# Ethernet2.net
KiCad netlist of a schematic drawn in Altium Designer
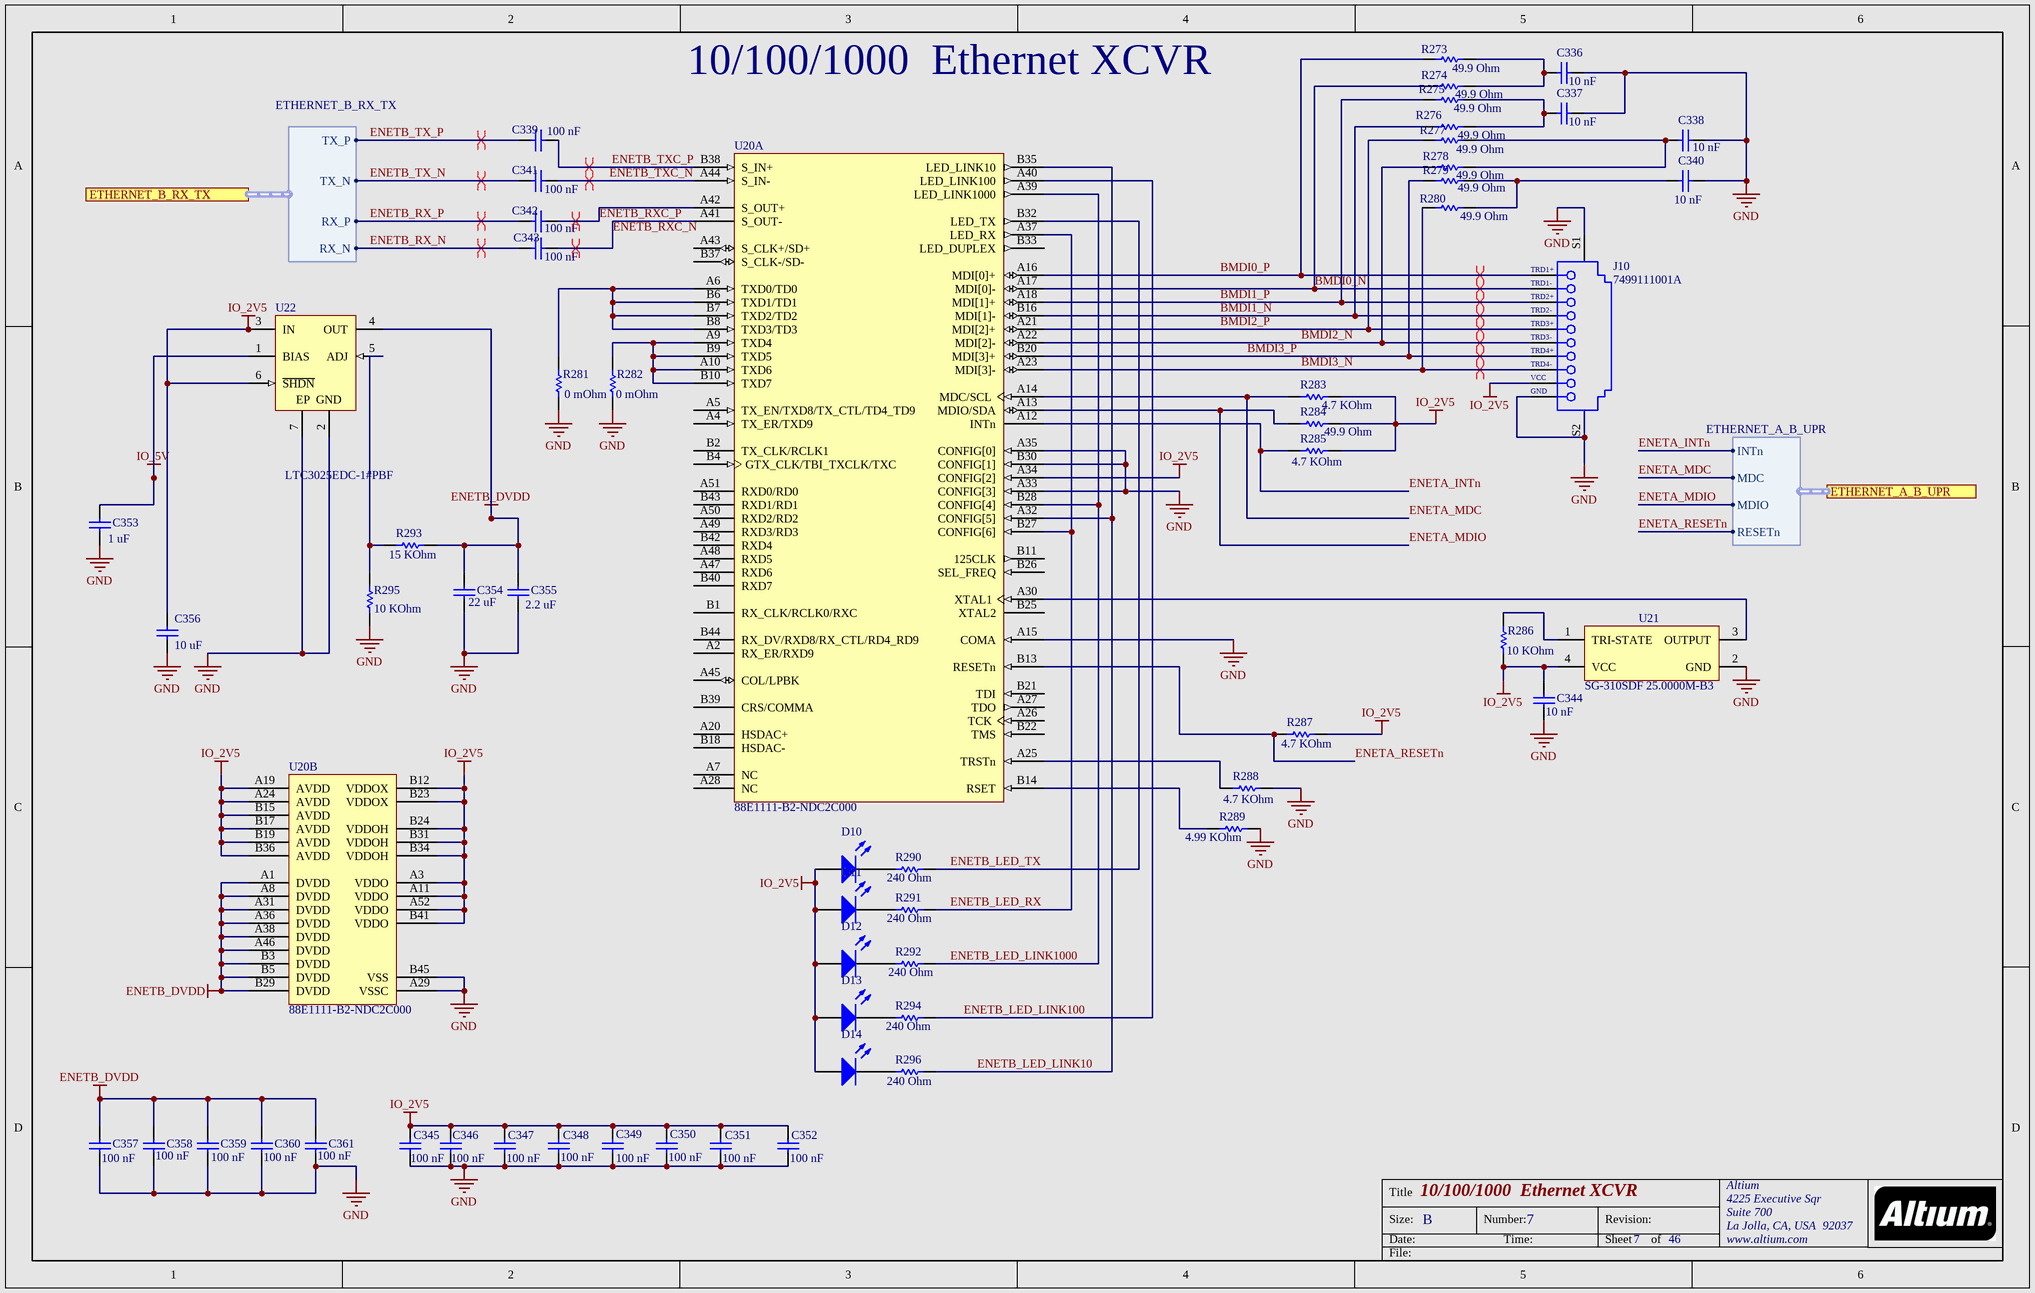
[diagram p0: Ethernet2.SchDoc]

(export (version "E")
  (design (tool "Eeschema 10.0.6"))
  (components
    (comp (ref "C336")
      (value "GRM155R71H103KA88D")
      (footprint "CAPC1005X55X25ML05T10")
      (description "Chip Capacitor, 10 nF, +/- 10%, 50 V, -55 to 125 degC, 0402 (1005 Metric), RoHS, Tape and Reel")
      (fields
        (field (name "TOLERANCE") "10%")
        (field (name "CAPACITANCE") "10 nF")
        (field (name "MANUFACTURER") "Basic Passives")
      )
      (libsource (lib "") (part "CAP-NP-2_1"))
    )
    (comp (ref "C337")
      (value "GRM155R71H103KA88D")
      (footprint "CAPC1005X55X25ML05T10")
      (description "Chip Capacitor, 10 nF, +/- 10%, 50 V, -55 to 125 degC, 0402 (1005 Metric), RoHS, Tape and Reel")
      (fields
        (field (name "TOLERANCE") "10%")
        (field (name "CAPACITANCE") "10 nF")
        (field (name "MANUFACTURER") "Basic Passives")
      )
      (libsource (lib "") (part "CAP-NP-2_1"))
    )
    (comp (ref "C338")
      (value "GRM155R71H103KA88D")
      (footprint "CAPC1005X55X25ML05T10")
      (description "Chip Capacitor, 10 nF, +/- 10%, 50 V, -55 to 125 degC, 0402 (1005 Metric), RoHS, Tape and Reel")
      (fields
        (field (name "TOLERANCE") "10%")
        (field (name "CAPACITANCE") "10 nF")
        (field (name "MANUFACTURER") "Basic Passives")
      )
      (libsource (lib "") (part "CAP-NP-2_1"))
    )
    (comp (ref "C339")
      (value "C1005X7R1E104M")
      (footprint "CAPC1005X55X10LL05")
      (description "Chip Capacitor, 0.1 uF, +/- 20%, 25 V, -55 to 125 degC, 0402 (1005 Metric), RoHS, Tape and Reel")
      (fields (field (name "TOLERANCE") "20%") (field (name "CAPACITANCE") "100 nF"))
      (libsource (lib "") (part "CAP-NP-2_1"))
    )
    (comp (ref "C340")
      (value "GRM155R71H103KA88D")
      (footprint "CAPC1005X55X25ML05T10")
      (description "Chip Capacitor, 10 nF, +/- 10%, 50 V, -55 to 125 degC, 0402 (1005 Metric), RoHS, Tape and Reel")
      (fields
        (field (name "TOLERANCE") "10%")
        (field (name "CAPACITANCE") "10 nF")
        (field (name "MANUFACTURER") "Basic Passives")
      )
      (libsource (lib "") (part "CAP-NP-2_1"))
    )
    (comp (ref "C341")
      (value "C1005X7R1E104M")
      (footprint "CAPC1005X55X10LL05")
      (description "Chip Capacitor, 0.1 uF, +/- 20%, 25 V, -55 to 125 degC, 0402 (1005 Metric), RoHS, Tape and Reel")
      (fields (field (name "TOLERANCE") "20%") (field (name "CAPACITANCE") "100 nF"))
      (libsource (lib "") (part "CAP-NP-2_1"))
    )
    (comp (ref "C342")
      (value "C1005X7R1E104M")
      (footprint "CAPC1005X55X10LL05")
      (description "Chip Capacitor, 0.1 uF, +/- 20%, 25 V, -55 to 125 degC, 0402 (1005 Metric), RoHS, Tape and Reel")
      (fields (field (name "TOLERANCE") "20%") (field (name "CAPACITANCE") "100 nF"))
      (libsource (lib "") (part "CAP-NP-2_1"))
    )
    (comp (ref "C343")
      (value "C1005X7R1E104M")
      (footprint "CAPC1005X55X10LL05")
      (description "Chip Capacitor, 0.1 uF, +/- 20%, 25 V, -55 to 125 degC, 0402 (1005 Metric), RoHS, Tape and Reel")
      (fields (field (name "TOLERANCE") "20%") (field (name "CAPACITANCE") "100 nF"))
      (libsource (lib "") (part "CAP-NP-2_1"))
    )
    (comp (ref "C344")
      (value "GRM155R71H103KA88D")
      (footprint "CAPC1005X55X25ML05T10")
      (description "Chip Capacitor, 10 nF, +/- 10%, 50 V, -55 to 125 degC, 0402 (1005 Metric), RoHS, Tape and Reel")
      (fields
        (field (name "TOLERANCE") "10%")
        (field (name "CAPACITANCE") "10 nF")
        (field (name "MANUFACTURER") "Basic Passives")
      )
      (libsource (lib "") (part "CAP-NP-2_1"))
    )
    (comp (ref "C345")
      (value "C1005X7R1E104M")
      (footprint "CAPC1005X55X10LL05")
      (description "Chip Capacitor, 0.1 uF, +/- 20%, 25 V, -55 to 125 degC, 0402 (1005 Metric), RoHS, Tape and Reel")
      (fields (field (name "TOLERANCE") "20%") (field (name "CAPACITANCE") "100 nF"))
      (libsource (lib "") (part "CAP-NP-2_1"))
    )
    (comp (ref "C346")
      (value "C1005X7R1E104M")
      (footprint "CAPC1005X55X10LL05")
      (description "Chip Capacitor, 0.1 uF, +/- 20%, 25 V, -55 to 125 degC, 0402 (1005 Metric), RoHS, Tape and Reel")
      (fields (field (name "TOLERANCE") "20%") (field (name "CAPACITANCE") "100 nF"))
      (libsource (lib "") (part "CAP-NP-2_1"))
    )
    (comp (ref "C347")
      (value "C1005X7R1E104M")
      (footprint "CAPC1005X55X10LL05")
      (description "Chip Capacitor, 0.1 uF, +/- 20%, 25 V, -55 to 125 degC, 0402 (1005 Metric), RoHS, Tape and Reel")
      (fields (field (name "TOLERANCE") "20%") (field (name "CAPACITANCE") "100 nF"))
      (libsource (lib "") (part "CAP-NP-2_1"))
    )
    (comp (ref "C348")
      (value "C1005X7R1E104M")
      (footprint "CAPC1005X55X10LL05")
      (description "Chip Capacitor, 0.1 uF, +/- 20%, 25 V, -55 to 125 degC, 0402 (1005 Metric), RoHS, Tape and Reel")
      (fields (field (name "TOLERANCE") "20%") (field (name "CAPACITANCE") "100 nF"))
      (libsource (lib "") (part "CAP-NP-2_1"))
    )
    (comp (ref "C349")
      (value "C1005X7R1E104M")
      (footprint "CAPC1005X55X10LL05")
      (description "Chip Capacitor, 0.1 uF, +/- 20%, 25 V, -55 to 125 degC, 0402 (1005 Metric), RoHS, Tape and Reel")
      (fields (field (name "TOLERANCE") "20%") (field (name "CAPACITANCE") "100 nF"))
      (libsource (lib "") (part "CAP-NP-2_1"))
    )
    (comp (ref "C350")
      (value "C1005X7R1E104M")
      (footprint "CAPC1005X55X10LL05")
      (description "Chip Capacitor, 0.1 uF, +/- 20%, 25 V, -55 to 125 degC, 0402 (1005 Metric), RoHS, Tape and Reel")
      (fields (field (name "TOLERANCE") "20%") (field (name "CAPACITANCE") "100 nF"))
      (libsource (lib "") (part "CAP-NP-2_1"))
    )
    (comp (ref "C351")
      (value "C1005X7R1E104M")
      (footprint "CAPC1005X55X10LL05")
      (description "Chip Capacitor, 0.1 uF, +/- 20%, 25 V, -55 to 125 degC, 0402 (1005 Metric), RoHS, Tape and Reel")
      (fields (field (name "TOLERANCE") "20%") (field (name "CAPACITANCE") "100 nF"))
      (libsource (lib "") (part "CAP-NP-2_1"))
    )
    (comp (ref "C352")
      (value "C1005X7R1E104M")
      (footprint "CAPC1005X55X10LL05")
      (description "Chip Capacitor, 0.1 uF, +/- 20%, 25 V, -55 to 125 degC, 0402 (1005 Metric), RoHS, Tape and Reel")
      (fields (field (name "TOLERANCE") "20%") (field (name "CAPACITANCE") "100 nF"))
      (libsource (lib "") (part "CAP-NP-2_1"))
    )
    (comp (ref "C353")
      (value "CGB2A1X5R1E105K033BC")
      (footprint "CAPC1005X33X10LL5")
      (description "Chip Capacitor, 1 uF, +/- 10%, 25 V, -55 to 85 degC, 0402 (1005 Metric), RoHS, Tape and Reel")
      (fields (field (name "CAPACITANCE") "1 uF") (field (name "TOLERANCE") "10%"))
      (libsource (lib "Altium Content Vault") (part "CAP-NP-2"))
    )
    (comp (ref "C354")
      (value "GRM31CR61E226KE15L")
      (footprint "CAPC3216X180X55ML20T25")
      (description "Chip Capacitor, 22 uF, +/- 10%, 25 V, -55 to 85 degC, 1206 (3216 Metric), RoHS, Tape and Reel")
      (fields (field (name "TOLERANCE") "10%") (field (name "CAPACITANCE") "22 uF"))
      (libsource (lib "") (part "CAP-NP-2_1"))
    )
    (comp (ref "C355")
      (value "GRM188R61A225KE34x")
      (footprint "CAPC1608X90X35ML10T15")
      (description "Chip Capacitor, 2.2 uF, +/- 10%, 10 V, -55 to 85 degC, 0603 (1608 Metric), RoHS, Tape and Reel")
      (fields (field (name "TOLERANCE") "10%") (field (name "CAPACITANCE") "2.2 uF"))
      (libsource (lib "Altium Content Vault") (part "CAP-NP-2"))
    )
    (comp (ref "C356")
      (value "C2012X5R1C106K085AC")
      (footprint "CAPC2013X100X20NL20")
      (description "Chip Capacitor, 10 uF, +/- 10%, 16 V, -55 to 85 degC, 0805 (2012 Metric), RoHS, Tape and Reel")
      (fields (field (name "TOLERANCE") "10%") (field (name "CAPACITANCE") "10 uF"))
      (libsource (lib "Altium Content Vault") (part "CAP-NP-2"))
    )
    (comp (ref "C357")
      (value "C1005X7R1E104M")
      (footprint "CAPC1005X55X10LL05")
      (description "Chip Capacitor, 0.1 uF, +/- 20%, 25 V, -55 to 125 degC, 0402 (1005 Metric), RoHS, Tape and Reel")
      (fields (field (name "TOLERANCE") "20%") (field (name "CAPACITANCE") "100 nF"))
      (libsource (lib "") (part "CAP-NP-2_1"))
    )
    (comp (ref "C358")
      (value "C1005X7R1E104M")
      (footprint "CAPC1005X55X10LL05")
      (description "Chip Capacitor, 0.1 uF, +/- 20%, 25 V, -55 to 125 degC, 0402 (1005 Metric), RoHS, Tape and Reel")
      (fields (field (name "TOLERANCE") "20%") (field (name "CAPACITANCE") "100 nF"))
      (libsource (lib "") (part "CAP-NP-2_1"))
    )
    (comp (ref "C359")
      (value "C1005X7R1E104M")
      (footprint "CAPC1005X55X10LL05")
      (description "Chip Capacitor, 0.1 uF, +/- 20%, 25 V, -55 to 125 degC, 0402 (1005 Metric), RoHS, Tape and Reel")
      (fields (field (name "TOLERANCE") "20%") (field (name "CAPACITANCE") "100 nF"))
      (libsource (lib "") (part "CAP-NP-2_1"))
    )
    (comp (ref "C360")
      (value "C1005X7R1E104M")
      (footprint "CAPC1005X55X10LL05")
      (description "Chip Capacitor, 0.1 uF, +/- 20%, 25 V, -55 to 125 degC, 0402 (1005 Metric), RoHS, Tape and Reel")
      (fields (field (name "TOLERANCE") "20%") (field (name "CAPACITANCE") "100 nF"))
      (libsource (lib "") (part "CAP-NP-2_1"))
    )
    (comp (ref "C361")
      (value "C1005X7R1E104M")
      (footprint "CAPC1005X55X10LL05")
      (description "Chip Capacitor, 0.1 uF, +/- 20%, 25 V, -55 to 125 degC, 0402 (1005 Metric), RoHS, Tape and Reel")
      (fields (field (name "TOLERANCE") "20%") (field (name "CAPACITANCE") "100 nF"))
      (libsource (lib "") (part "CAP-NP-2_1"))
    )
    (comp (ref "D10")
      (value "150060VS75000")
      (footprint "0603_A")
      (description "SMD mono-color Chip LED, WL-SMCW, Bright Green")
      (fields (field (name "MANUFACTURER") "Wuerth Elektronik"))
      (libsource (lib "Altium Content Vault") (part "CMP-1426-00006-1"))
    )
    (comp (ref "D11")
      (value "150060VS75000")
      (footprint "0603_A")
      (description "SMD mono-color Chip LED, WL-SMCW, Bright Green")
      (fields (field (name "MANUFACTURER") "Wuerth Elektronik"))
      (libsource (lib "Altium Content Vault") (part "CMP-1426-00006-1"))
    )
    (comp (ref "D12")
      (value "150060VS75000")
      (footprint "0603_A")
      (description "SMD mono-color Chip LED, WL-SMCW, Bright Green")
      (fields (field (name "MANUFACTURER") "Wuerth Elektronik"))
      (libsource (lib "Altium Content Vault") (part "CMP-1426-00006-1"))
    )
    (comp (ref "D13")
      (value "150060VS75000")
      (footprint "0603_A")
      (description "SMD mono-color Chip LED, WL-SMCW, Bright Green")
      (fields (field (name "MANUFACTURER") "Wuerth Elektronik"))
      (libsource (lib "Altium Content Vault") (part "CMP-1426-00006-1"))
    )
    (comp (ref "D14")
      (value "150060VS75000")
      (footprint "0603_A")
      (description "SMD mono-color Chip LED, WL-SMCW, Bright Green")
      (fields (field (name "MANUFACTURER") "Wuerth Elektronik"))
      (libsource (lib "Altium Content Vault") (part "CMP-1426-00006-1"))
    )
    (comp (ref "J10")
      (value "7499111001A")
      (footprint "WE-7499111001A_V")
      (description "RJ45 LAN Transformer, Modular JACK, 0 to 70 degC, 10-Pin THD, RoHS, Tube")
      (libsource (lib "Altium Content Vault") (part "RJ45-10-2SHLD_A"))
    )
    (comp (ref "R273")
      (value "NRC04F49R9TRF")
      (footprint "RESC1005X35X25NL8T10")
      (description "Chip Resistor, 49.9 Ohm, +/- 1%, 0.06 W, -55 to 155 degC, 0402 (1005 Metric), RoHS, Tape and Reel")
      (fields (field (name "TOLERANCE") "1%") (field (name "RESISTANCE") "49.9 Ohm"))
      (libsource (lib "Altium Content Vault") (part "CMP-1599-00001-2"))
    )
    (comp (ref "R274")
      (value "NRC04F49R9TRF")
      (footprint "RESC1005X35X25NL8T10")
      (description "Chip Resistor, 49.9 Ohm, +/- 1%, 0.06 W, -55 to 155 degC, 0402 (1005 Metric), RoHS, Tape and Reel")
      (fields (field (name "TOLERANCE") "1%") (field (name "RESISTANCE") "49.9 Ohm"))
      (libsource (lib "Altium Content Vault") (part "RES-2"))
    )
    (comp (ref "R275")
      (value "NRC04F49R9TRF")
      (footprint "RESC1005X35X25NL8T10")
      (description "Chip Resistor, 49.9 Ohm, +/- 1%, 0.06 W, -55 to 155 degC, 0402 (1005 Metric), RoHS, Tape and Reel")
      (fields (field (name "TOLERANCE") "1%") (field (name "RESISTANCE") "49.9 Ohm"))
      (libsource (lib "Altium Content Vault") (part "RES-2"))
    )
    (comp (ref "R276")
      (value "NRC04F49R9TRF")
      (footprint "RESC1005X35X25NL8T10")
      (description "Chip Resistor, 49.9 Ohm, +/- 1%, 0.06 W, -55 to 155 degC, 0402 (1005 Metric), RoHS, Tape and Reel")
      (fields (field (name "TOLERANCE") "1%") (field (name "RESISTANCE") "49.9 Ohm"))
      (libsource (lib "Altium Content Vault") (part "CMP-1599-00001-2"))
    )
    (comp (ref "R277")
      (value "NRC04F49R9TRF")
      (footprint "RESC1005X35X25NL8T10")
      (description "Chip Resistor, 49.9 Ohm, +/- 1%, 0.06 W, -55 to 155 degC, 0402 (1005 Metric), RoHS, Tape and Reel")
      (fields (field (name "TOLERANCE") "1%") (field (name "RESISTANCE") "49.9 Ohm"))
      (libsource (lib "Altium Content Vault") (part "RES-2"))
    )
    (comp (ref "R278")
      (value "NRC04F49R9TRF")
      (footprint "RESC1005X35X25NL8T10")
      (description "Chip Resistor, 49.9 Ohm, +/- 1%, 0.06 W, -55 to 155 degC, 0402 (1005 Metric), RoHS, Tape and Reel")
      (fields (field (name "TOLERANCE") "1%") (field (name "RESISTANCE") "49.9 Ohm"))
      (libsource (lib "Altium Content Vault") (part "RES-2"))
    )
    (comp (ref "R279")
      (value "NRC04F49R9TRF")
      (footprint "RESC1005X35X25NL8T10")
      (description "Chip Resistor, 49.9 Ohm, +/- 1%, 0.06 W, -55 to 155 degC, 0402 (1005 Metric), RoHS, Tape and Reel")
      (fields (field (name "TOLERANCE") "1%") (field (name "RESISTANCE") "49.9 Ohm"))
      (libsource (lib "Altium Content Vault") (part "CMP-1599-00001-2"))
    )
    (comp (ref "R280")
      (value "NRC04F49R9TRF")
      (footprint "RESC1005X35X25NL8T10")
      (description "Chip Resistor, 49.9 Ohm, +/- 1%, 0.06 W, -55 to 155 degC, 0402 (1005 Metric), RoHS, Tape and Reel")
      (fields (field (name "TOLERANCE") "1%") (field (name "RESISTANCE") "49.9 Ohm"))
      (libsource (lib "Altium Content Vault") (part "RES-2"))
    )
    (comp (ref "R281")
      (value "ERJ-2GE0R00X")
      (footprint "RESC1005X40X25ML05T05")
      (description "Chip Resistor, 0 mOhm, +/- 5%, 100 mW, -55 to 155 degC, 0402 (1005 Metric), RoHS, Tape and Reel")
      (fields
        (field (name "TOLERANCE") "5%")
        (field (name "RESISTANCE") "0 mOhm")
        (field (name "MANUFACTURER") "Basic Passives")
      )
      (libsource (lib "Altium Content Vault") (part "RES-2"))
    )
    (comp (ref "R282")
      (value "ERJ-2GE0R00X")
      (footprint "RESC1005X40X25ML05T05")
      (description "Chip Resistor, 0 mOhm, +/- 5%, 100 mW, -55 to 155 degC, 0402 (1005 Metric), RoHS, Tape and Reel")
      (fields
        (field (name "TOLERANCE") "5%")
        (field (name "RESISTANCE") "0 mOhm")
        (field (name "MANUFACTURER") "Basic Passives")
      )
      (libsource (lib "Altium Content Vault") (part "RES-2"))
    )
    (comp (ref "R283")
      (value "ERJ-2RKF4701X")
      (footprint "RESC1005X40X25LL05T05")
      (description "Chip Resistor, 4.7 KOhm, +/- 1%, 0.1 W, -55 to 155 degC, 0402 (1005 Metric), RoHS, Tape and Reel")
      (fields (field (name "TOLERANCE") "1%") (field (name "RESISTANCE") "4.7 KOhm"))
      (libsource (lib "Altium Content Vault") (part "RES-2"))
    )
    (comp (ref "R284")
      (value "NRC04F49R9TRF")
      (footprint "RESC1005X35X25NL8T10")
      (description "Chip Resistor, 49.9 Ohm, +/- 1%, 0.06 W, -55 to 155 degC, 0402 (1005 Metric), RoHS, Tape and Reel")
      (fields (field (name "TOLERANCE") "1%") (field (name "RESISTANCE") "49.9 Ohm"))
      (libsource (lib "Altium Content Vault") (part "CMP-1599-00001-2"))
    )
    (comp (ref "R285")
      (value "ERJ-2RKF4701X")
      (footprint "RESC1005X40X25LL05T05")
      (description "Chip Resistor, 4.7 KOhm, +/- 1%, 0.1 W, -55 to 155 degC, 0402 (1005 Metric), RoHS, Tape and Reel")
      (fields (field (name "TOLERANCE") "1%") (field (name "RESISTANCE") "4.7 KOhm"))
      (libsource (lib "Altium Content Vault") (part "RES-2"))
    )
    (comp (ref "R286")
      (value "ERJ-2RKF1002X")
      (footprint "RESC1005X40X25NL05T05")
      (description "Chip Resistor, 10 KOhm, +/- 1%, 100 mW, -55 to 155 degC, 0402 (1005 Metric), RoHS, Tape and Reel")
      (fields
        (field (name "TOLERANCE") "1%")
        (field (name "RESISTANCE") "10 KOhm")
        (field (name "MANUFACTURER") "Basic Passives")
      )
      (libsource (lib "Altium Content Vault") (part "RES-2"))
    )
    (comp (ref "R287")
      (value "ERJ-2RKF4701X")
      (footprint "RESC1005X40X25LL05T05")
      (description "Chip Resistor, 4.7 KOhm, +/- 1%, 0.1 W, -55 to 155 degC, 0402 (1005 Metric), RoHS, Tape and Reel")
      (fields (field (name "TOLERANCE") "1%") (field (name "RESISTANCE") "4.7 KOhm"))
      (libsource (lib "Altium Content Vault") (part "RES-2"))
    )
    (comp (ref "R288")
      (value "ERJ-2RKF4701X")
      (footprint "RESC1005X40X25LL05T05")
      (description "Chip Resistor, 4.7 KOhm, +/- 1%, 0.1 W, -55 to 155 degC, 0402 (1005 Metric), RoHS, Tape and Reel")
      (fields (field (name "TOLERANCE") "1%") (field (name "RESISTANCE") "4.7 KOhm"))
      (libsource (lib "Altium Content Vault") (part "RES-2"))
    )
    (comp (ref "R289")
      (value "ERJ-2RKF4991X")
      (footprint "RESC1005X40X25NL05T05")
      (description "Chip Resistor, 4.99 KOhm, +/- 1%, 100 mW, -55 to 155 degC, 0402 (1005 Metric), RoHS, Tape and Reel")
      (fields
        (field (name "TOLERANCE") "1%")
        (field (name "RESISTANCE") "4.99 KOhm")
        (field (name "MANUFACTURER") "Basic Passives")
      )
      (libsource (lib "Altium Content Vault") (part "RES-2"))
    )
    (comp (ref "R290")
      (value "ERJ-2RKF2400X")
      (footprint "RESC1005X40X25NL05T05")
      (description "Chip Resistor, 240 Ohm, +/- 1%, 100 mW, -55 to 155 degC, 0402 (1005 Metric), RoHS, Tape and Reel")
      (fields (field (name "TOLERANCE") "1%") (field (name "RESISTANCE") "240 Ohm"))
      (libsource (lib "Altium Content Vault") (part "RES-2"))
    )
    (comp (ref "R291")
      (value "ERJ-2RKF2400X")
      (footprint "RESC1005X40X25NL05T05")
      (description "Chip Resistor, 240 Ohm, +/- 1%, 100 mW, -55 to 155 degC, 0402 (1005 Metric), RoHS, Tape and Reel")
      (fields (field (name "TOLERANCE") "1%") (field (name "RESISTANCE") "240 Ohm"))
      (libsource (lib "Altium Content Vault") (part "RES-2"))
    )
    (comp (ref "R292")
      (value "ERJ-2RKF2400X")
      (footprint "RESC1005X40X25NL05T05")
      (description "Chip Resistor, 240 Ohm, +/- 1%, 100 mW, -55 to 155 degC, 0402 (1005 Metric), RoHS, Tape and Reel")
      (fields (field (name "TOLERANCE") "1%") (field (name "RESISTANCE") "240 Ohm"))
      (libsource (lib "Altium Content Vault") (part "RES-2"))
    )
    (comp (ref "R293")
      (value "ERJ-2RKF1502X")
      (footprint "RESC1005X40X25ML05T05")
      (description "Chip Resistor, 15 KOhm, +/- 1%, 100 mW, -55 to 155 degC, 0402 (1005 Metric), RoHS, Tape and Reel")
      (fields
        (field (name "RESISTANCE") "15 KOhm")
        (field (name "TOLERANCE") "1%")
        (field (name "MANUFACTURER") "Basic Passives")
      )
      (libsource (lib "Altium Content Vault") (part "RES-2"))
    )
    (comp (ref "R294")
      (value "ERJ-2RKF2400X")
      (footprint "RESC1005X40X25NL05T05")
      (description "Chip Resistor, 240 Ohm, +/- 1%, 100 mW, -55 to 155 degC, 0402 (1005 Metric), RoHS, Tape and Reel")
      (fields (field (name "TOLERANCE") "1%") (field (name "RESISTANCE") "240 Ohm"))
      (libsource (lib "Altium Content Vault") (part "RES-2"))
    )
    (comp (ref "R295")
      (value "ERJ-2RKF1002X")
      (footprint "RESC1005X40X25NL05T05")
      (description "Chip Resistor, 10 KOhm, +/- 1%, 100 mW, -55 to 155 degC, 0402 (1005 Metric), RoHS, Tape and Reel")
      (fields
        (field (name "TOLERANCE") "1%")
        (field (name "RESISTANCE") "10 KOhm")
        (field (name "MANUFACTURER") "Basic Passives")
      )
      (libsource (lib "Altium Content Vault") (part "RES-2"))
    )
    (comp (ref "R296")
      (value "ERJ-2RKF2400X")
      (footprint "RESC1005X40X25NL05T05")
      (description "Chip Resistor, 240 Ohm, +/- 1%, 100 mW, -55 to 155 degC, 0402 (1005 Metric), RoHS, Tape and Reel")
      (fields (field (name "TOLERANCE") "1%") (field (name "RESISTANCE") "240 Ohm"))
      (libsource (lib "Altium Content Vault") (part "RES-2"))
    )
    (comp (ref "U20")
      (value "88E1111-B2-NDC2C000")
      (footprint "MARV-NDC96")
      (description "Integrated 10/100/1000 Ultra Gigabit Ethernet Transceiver, Commercial Grade, 96-Pin QFN, RoHS")
      (libsource (lib "Altium Content Vault") (part "MARV-88E1111-NDC96"))
    )
    (comp (ref "U21")
      (value "SG-310SDF 25.0000M-B3")
      (footprint "EPSON-SG-310-4_V")
      (description "Crystal Oscillator (SPXO), 2.5 V, 25 MHz, -20 to 70 degC, 4-Pin SMD, RoHS, Tape and Reel")
      (libsource (lib "Altium Content Vault") (part "XTAL-1-3-4_B"))
    )
    (comp (ref "U22")
      (value "LTC3025EDC-1#PBF")
      (footprint "LT-DC6-6_V")
      (fields (field (name "MANUFACTURER") "Linear Technology"))
      (libsource (lib "Altium Content Vault") (part "LT-LTC302-DC6-6"))
    )
  )
  (nets
    (net (code "3") (name "/BMDI0_N") (class "Default")
      (node (ref "J10") (pin "2") (pinfunction "TRD1-_2") (pintype "passive"))
      (node (ref "R274") (pin "1") (pinfunction "1_1") (pintype "passive"))
      (node (ref "U20") (pin "A17") (pinfunction "MDI[0]-_A17") (pintype "bidirectional"))
    )
    (net (code "4") (name "/BMDI0_P") (class "Default")
      (node (ref "J10") (pin "1") (pinfunction "TRD1+_1") (pintype "passive"))
      (node (ref "R273") (pin "1") (pinfunction "1_1") (pintype "passive"))
      (node (ref "U20") (pin "A16") (pinfunction "MDI[0]+_A16") (pintype "bidirectional"))
    )
    (net (code "5") (name "/BMDI1_N") (class "Default")
      (node (ref "J10") (pin "4") (pinfunction "TRD2-_4") (pintype "passive"))
      (node (ref "R276") (pin "1") (pinfunction "1_1") (pintype "passive"))
      (node (ref "U20") (pin "B16") (pinfunction "MDI[1]-_B16") (pintype "bidirectional"))
    )
    (net (code "6") (name "/BMDI1_P") (class "Default")
      (node (ref "J10") (pin "3") (pinfunction "TRD2+_3") (pintype "passive"))
      (node (ref "R275") (pin "1") (pinfunction "1_1") (pintype "passive"))
      (node (ref "U20") (pin "A18") (pinfunction "MDI[1]+_A18") (pintype "bidirectional"))
    )
    (net (code "7") (name "/BMDI2_N") (class "Default")
      (node (ref "J10") (pin "6") (pinfunction "TRD3-_6") (pintype "passive"))
      (node (ref "R278") (pin "1") (pinfunction "1_1") (pintype "passive"))
      (node (ref "U20") (pin "A22") (pinfunction "MDI[2]-_A22") (pintype "bidirectional"))
    )
    (net (code "8") (name "/BMDI2_P") (class "Default")
      (node (ref "J10") (pin "5") (pinfunction "TRD3+_5") (pintype "passive"))
      (node (ref "R277") (pin "1") (pinfunction "1_1") (pintype "passive"))
      (node (ref "U20") (pin "A21") (pinfunction "MDI[2]+_A21") (pintype "bidirectional"))
    )
    (net (code "9") (name "/BMDI3_N") (class "Default")
      (node (ref "J10") (pin "8") (pinfunction "TRD4-_8") (pintype "passive"))
      (node (ref "R280") (pin "1") (pinfunction "1_1") (pintype "passive"))
      (node (ref "U20") (pin "A23") (pinfunction "MDI[3]-_A23") (pintype "bidirectional"))
    )
    (net (code "10") (name "/BMDI3_P") (class "Default")
      (node (ref "J10") (pin "7") (pinfunction "TRD4+_7") (pintype "passive"))
      (node (ref "R279") (pin "1") (pinfunction "1_1") (pintype "passive"))
      (node (ref "U20") (pin "B20") (pinfunction "MDI[3]+_B20") (pintype "bidirectional"))
    )
    (net (code "11") (name "/ENETA_INTn") (class "Default")
      (node (ref "R285") (pin "1") (pinfunction "1_1") (pintype "passive"))
      (node (ref "U20") (pin "A12") (pinfunction "INTn_A12") (pintype "passive"))
    )
    (net (code "12") (name "/ENETA_MDC") (class "Default")
      (node (ref "R283") (pin "1") (pinfunction "1_1") (pintype "passive"))
      (node (ref "U20") (pin "A14") (pinfunction "MDC/SCL_A14") (pintype "input"))
    )
    (net (code "13") (name "/ENETA_MDIO") (class "Default")
      (node (ref "R284") (pin "1") (pinfunction "1_1") (pintype "passive"))
      (node (ref "U20") (pin "A13") (pinfunction "MDIO/SDA_A13") (pintype "bidirectional"))
    )
    (net (code "14") (name "/ENETA_RESETn") (class "Default")
      (node (ref "R287") (pin "1") (pinfunction "1_1") (pintype "passive"))
      (node (ref "U20") (pin "B13") (pinfunction "RESETn_B13") (pintype "input"))
    )
    (net (code "15") (name "/ENETB_LED_LINK10") (class "Default")
      (node (ref "R296") (pin "2") (pinfunction "2_2") (pintype "passive"))
      (node (ref "U20") (pin "A32") (pinfunction "CONFIG[5]_A32") (pintype "input"))
      (node (ref "U20") (pin "B35") (pinfunction "LED_LINK10_B35") (pintype "output"))
    )
    (net (code "16") (name "/ENETB_LED_LINK100") (class "Default")
      (node (ref "R294") (pin "2") (pinfunction "2_2") (pintype "passive"))
      (node (ref "U20") (pin "A40") (pinfunction "LED_LINK100_A40") (pintype "output"))
    )
    (net (code "17") (name "/ENETB_LED_LINK1000") (class "Default")
      (node (ref "R292") (pin "2") (pinfunction "2_2") (pintype "passive"))
      (node (ref "U20") (pin "A39") (pinfunction "LED_LINK1000_A39") (pintype "output"))
      (node (ref "U20") (pin "B28") (pinfunction "CONFIG[4]_B28") (pintype "input"))
    )
    (net (code "18") (name "/ENETB_LED_RX") (class "Default")
      (node (ref "R291") (pin "2") (pinfunction "2_2") (pintype "passive"))
      (node (ref "U20") (pin "A37") (pinfunction "LED_RX_A37") (pintype "output"))
      (node (ref "U20") (pin "B27") (pinfunction "CONFIG[6]_B27") (pintype "input"))
    )
    (net (code "19") (name "/ENETB_LED_TX") (class "Default")
      (node (ref "R290") (pin "2") (pinfunction "2_2") (pintype "passive"))
      (node (ref "U20") (pin "B32") (pinfunction "LED_TX_B32") (pintype "output"))
    )
    (net (code "20") (name "/ENETB_RXC_N") (class "Default")
      (node (ref "C343") (pin "2") (pinfunction "2_2") (pintype "passive"))
      (node (ref "U20") (pin "A41") (pinfunction "S_OUT-_A41") (pintype "tri_state"))
    )
    (net (code "21") (name "/ENETB_RXC_P") (class "Default")
      (node (ref "C342") (pin "2") (pinfunction "2_2") (pintype "passive"))
      (node (ref "U20") (pin "A42") (pinfunction "S_OUT+_A42") (pintype "tri_state"))
    )
    (net (code "22") (name "/ENETB_RX_N") (class "Default")
      (node (ref "C343") (pin "1") (pinfunction "1_1") (pintype "passive"))
    )
    (net (code "23") (name "/ENETB_RX_P") (class "Default")
      (node (ref "C342") (pin "1") (pinfunction "1_1") (pintype "passive"))
    )
    (net (code "24") (name "/ENETB_TXC_N") (class "Default")
      (node (ref "C341") (pin "2") (pinfunction "2_2") (pintype "passive"))
      (node (ref "U20") (pin "A44") (pinfunction "S_IN-_A44") (pintype "input"))
    )
    (net (code "25") (name "/ENETB_TXC_P") (class "Default")
      (node (ref "C339") (pin "2") (pinfunction "2_2") (pintype "passive"))
      (node (ref "U20") (pin "B38") (pinfunction "S_IN+_B38") (pintype "input"))
    )
    (net (code "26") (name "/ENETB_TX_N") (class "Default")
      (node (ref "C341") (pin "1") (pinfunction "1_1") (pintype "passive"))
    )
    (net (code "27") (name "/ENETB_TX_P") (class "Default")
      (node (ref "C339") (pin "1") (pinfunction "1_1") (pintype "passive"))
    )
    (net (code "30") (name "ENETB_DVDD") (class "Default")
      (node (ref "C354") (pin "2") (pinfunction "2_2") (pintype "passive"))
      (node (ref "C355") (pin "2") (pinfunction "2_2") (pintype "passive"))
      (node (ref "C357") (pin "2") (pinfunction "2_2") (pintype "passive"))
      (node (ref "C358") (pin "2") (pinfunction "2_2") (pintype "passive"))
      (node (ref "C359") (pin "2") (pinfunction "2_2") (pintype "passive"))
      (node (ref "C360") (pin "2") (pinfunction "2_2") (pintype "passive"))
      (node (ref "C361") (pin "2") (pinfunction "2_2") (pintype "passive"))
      (node (ref "R293") (pin "2") (pinfunction "2_2") (pintype "passive"))
      (node (ref "U20") (pin "A1") (pinfunction "DVDD_A1") (pintype "power_in"))
      (node (ref "U20") (pin "A31") (pinfunction "DVDD_A31") (pintype "power_in"))
      (node (ref "U20") (pin "A36") (pinfunction "DVDD_A36") (pintype "power_in"))
      (node (ref "U20") (pin "A38") (pinfunction "DVDD_A38") (pintype "power_in"))
      (node (ref "U20") (pin "A46") (pinfunction "DVDD_A46") (pintype "power_in"))
      (node (ref "U20") (pin "A8") (pinfunction "DVDD_A8") (pintype "power_in"))
      (node (ref "U20") (pin "B29") (pinfunction "DVDD_B29") (pintype "power_in"))
      (node (ref "U20") (pin "B3") (pinfunction "DVDD_B3") (pintype "power_in"))
      (node (ref "U20") (pin "B5") (pinfunction "DVDD_B5") (pintype "power_in"))
      (node (ref "U22") (pin "4") (pinfunction "OUT_4") (pintype "power_in"))
    )
    (net (code "31") (name "GND") (class "Default")
      (node (ref "C336") (pin "2") (pinfunction "2_2") (pintype "passive"))
      (node (ref "C337") (pin "2") (pinfunction "2_2") (pintype "passive"))
      (node (ref "C338") (pin "2") (pinfunction "2_2") (pintype "passive"))
      (node (ref "C340") (pin "2") (pinfunction "2_2") (pintype "passive"))
      (node (ref "C344") (pin "1") (pinfunction "1_1") (pintype "passive"))
      (node (ref "C345") (pin "1") (pinfunction "1_1") (pintype "passive"))
      (node (ref "C346") (pin "1") (pinfunction "1_1") (pintype "passive"))
      (node (ref "C347") (pin "1") (pinfunction "1_1") (pintype "passive"))
      (node (ref "C348") (pin "1") (pinfunction "1_1") (pintype "passive"))
      (node (ref "C349") (pin "1") (pinfunction "1_1") (pintype "passive"))
      (node (ref "C350") (pin "1") (pinfunction "1_1") (pintype "passive"))
      (node (ref "C351") (pin "1") (pinfunction "1_1") (pintype "passive"))
      (node (ref "C352") (pin "1") (pinfunction "1_1") (pintype "passive"))
      (node (ref "C353") (pin "1") (pinfunction "1_1") (pintype "passive"))
      (node (ref "C354") (pin "1") (pinfunction "1_1") (pintype "passive"))
      (node (ref "C355") (pin "1") (pinfunction "1_1") (pintype "passive"))
      (node (ref "C356") (pin "1") (pinfunction "1_1") (pintype "passive"))
      (node (ref "C357") (pin "1") (pinfunction "1_1") (pintype "passive"))
      (node (ref "C358") (pin "1") (pinfunction "1_1") (pintype "passive"))
      (node (ref "C359") (pin "1") (pinfunction "1_1") (pintype "passive"))
      (node (ref "C360") (pin "1") (pinfunction "1_1") (pintype "passive"))
      (node (ref "C361") (pin "1") (pinfunction "1_1") (pintype "passive"))
      (node (ref "J10") (pin "10") (pinfunction "GND_10") (pintype "power_in"))
      (node (ref "J10") (pin "S1") (pinfunction "SHLD_S1") (pintype "passive"))
      (node (ref "J10") (pin "S2") (pinfunction "SHLD_S2") (pintype "passive"))
      (node (ref "R281") (pin "1") (pinfunction "1_1") (pintype "passive"))
      (node (ref "R282") (pin "1") (pinfunction "1_1") (pintype "passive"))
      (node (ref "R288") (pin "2") (pinfunction "2_2") (pintype "passive"))
      (node (ref "R289") (pin "2") (pinfunction "2_2") (pintype "passive"))
      (node (ref "R295") (pin "1") (pinfunction "1_1") (pintype "passive"))
      (node (ref "U20") (pin "A15") (pinfunction "COMA_A15") (pintype "input"))
      (node (ref "U20") (pin "A29") (pinfunction "VSSC_A29") (pintype "power_in"))
      (node (ref "U20") (pin "A33") (pinfunction "CONFIG[3]_A33") (pintype "input"))
      (node (ref "U20") (pin "A35") (pinfunction "CONFIG[0]_A35") (pintype "input"))
      (node (ref "U20") (pin "B30") (pinfunction "CONFIG[1]_B30") (pintype "input"))
      (node (ref "U20") (pin "B45") (pinfunction "VSS_B45") (pintype "power_in"))
      (node (ref "U21") (pin "2") (pinfunction "GND_2") (pintype "power_in"))
      (node (ref "U22") (pin "2") (pinfunction "GND_2") (pintype "power_in"))
      (node (ref "U22") (pin "7") (pinfunction "EP_7") (pintype "power_in"))
    )
    (net (code "32") (name "IO_2V5") (class "Default")
      (node (ref "C344") (pin "2") (pinfunction "2_2") (pintype "passive"))
      (node (ref "C345") (pin "2") (pinfunction "2_2") (pintype "passive"))
      (node (ref "C346") (pin "2") (pinfunction "2_2") (pintype "passive"))
      (node (ref "C347") (pin "2") (pinfunction "2_2") (pintype "passive"))
      (node (ref "C348") (pin "2") (pinfunction "2_2") (pintype "passive"))
      (node (ref "C349") (pin "2") (pinfunction "2_2") (pintype "passive"))
      (node (ref "C350") (pin "2") (pinfunction "2_2") (pintype "passive"))
      (node (ref "C351") (pin "2") (pinfunction "2_2") (pintype "passive"))
      (node (ref "C352") (pin "2") (pinfunction "2_2") (pintype "passive"))
      (node (ref "C356") (pin "2") (pinfunction "2_2") (pintype "passive"))
      (node (ref "D10") (pin "2") (pinfunction "A_2") (pintype "passive"))
      (node (ref "D11") (pin "2") (pinfunction "A_2") (pintype "passive"))
      (node (ref "D12") (pin "2") (pinfunction "A_2") (pintype "passive"))
      (node (ref "D13") (pin "2") (pinfunction "A_2") (pintype "passive"))
      (node (ref "D14") (pin "2") (pinfunction "A_2") (pintype "passive"))
      (node (ref "J10") (pin "9") (pinfunction "VCC_9") (pintype "power_in"))
      (node (ref "R283") (pin "2") (pinfunction "2_2") (pintype "passive"))
      (node (ref "R284") (pin "2") (pinfunction "2_2") (pintype "passive"))
      (node (ref "R285") (pin "2") (pinfunction "2_2") (pintype "passive"))
      (node (ref "R286") (pin "1") (pinfunction "1_1") (pintype "passive"))
      (node (ref "R287") (pin "2") (pinfunction "2_2") (pintype "passive"))
      (node (ref "U20") (pin "A11") (pinfunction "VDDO_A11") (pintype "power_in"))
      (node (ref "U20") (pin "A19") (pinfunction "AVDD_A19") (pintype "power_in"))
      (node (ref "U20") (pin "A24") (pinfunction "AVDD_A24") (pintype "power_in"))
      (node (ref "U20") (pin "A3") (pinfunction "VDDO_A3") (pintype "power_in"))
      (node (ref "U20") (pin "A34") (pinfunction "CONFIG[2]_A34") (pintype "input"))
      (node (ref "U20") (pin "A52") (pinfunction "VDDO_A52") (pintype "power_in"))
      (node (ref "U20") (pin "B12") (pinfunction "VDDOX_B12") (pintype "power_in"))
      (node (ref "U20") (pin "B15") (pinfunction "AVDD_B15") (pintype "power_in"))
      (node (ref "U20") (pin "B17") (pinfunction "AVDD_B17") (pintype "power_in"))
      (node (ref "U20") (pin "B19") (pinfunction "AVDD_B19") (pintype "power_in"))
      (node (ref "U20") (pin "B23") (pinfunction "VDDOX_B23") (pintype "power_in"))
      (node (ref "U20") (pin "B24") (pinfunction "VDDOH_B24") (pintype "power_in"))
      (node (ref "U20") (pin "B31") (pinfunction "VDDOH_B31") (pintype "power_in"))
      (node (ref "U20") (pin "B34") (pinfunction "VDDOH_B34") (pintype "power_in"))
      (node (ref "U20") (pin "B36") (pinfunction "AVDD_B36") (pintype "power_in"))
      (node (ref "U20") (pin "B41") (pinfunction "VDDO_B41") (pintype "power_in"))
      (node (ref "U21") (pin "4") (pinfunction "VCC_4") (pintype "power_in"))
      (node (ref "U22") (pin "3") (pinfunction "IN_3") (pintype "power_in"))
      (node (ref "U22") (pin "6") (pinfunction "~{SHDN}_6") (pintype "input"))
    )
    (net (code "33") (name "IO_5V") (class "Default")
      (node (ref "C353") (pin "2") (pinfunction "2_2") (pintype "passive"))
      (node (ref "U22") (pin "1") (pinfunction "BIAS_1") (pintype "power_in"))
    )
    (net (code "34") (name "Net-(C336-Pad1)") (class "Default")
      (node (ref "C336") (pin "1") (pinfunction "1_1") (pintype "passive"))
      (node (ref "R273") (pin "2") (pinfunction "2_2") (pintype "passive"))
      (node (ref "R274") (pin "2") (pinfunction "2_2") (pintype "passive"))
    )
    (net (code "35") (name "Net-(C337-Pad1)") (class "Default")
      (node (ref "C337") (pin "1") (pinfunction "1_1") (pintype "passive"))
      (node (ref "R275") (pin "2") (pinfunction "2_2") (pintype "passive"))
      (node (ref "R276") (pin "2") (pinfunction "2_2") (pintype "passive"))
    )
    (net (code "36") (name "Net-(C338-Pad1)") (class "Default")
      (node (ref "C338") (pin "1") (pinfunction "1_1") (pintype "passive"))
      (node (ref "R277") (pin "2") (pinfunction "2_2") (pintype "passive"))
      (node (ref "R278") (pin "2") (pinfunction "2_2") (pintype "passive"))
    )
    (net (code "37") (name "Net-(C340-Pad1)") (class "Default")
      (node (ref "C340") (pin "1") (pinfunction "1_1") (pintype "passive"))
      (node (ref "R279") (pin "2") (pinfunction "2_2") (pintype "passive"))
      (node (ref "R280") (pin "2") (pinfunction "2_2") (pintype "passive"))
    )
    (net (code "38") (name "Net-(D10-K)") (class "Default")
      (node (ref "D10") (pin "1") (pinfunction "K_1") (pintype "passive"))
      (node (ref "R290") (pin "1") (pinfunction "1_1") (pintype "passive"))
    )
    (net (code "39") (name "Net-(D11-K)") (class "Default")
      (node (ref "D11") (pin "1") (pinfunction "K_1") (pintype "passive"))
      (node (ref "R291") (pin "1") (pinfunction "1_1") (pintype "passive"))
    )
    (net (code "40") (name "Net-(D12-K)") (class "Default")
      (node (ref "D12") (pin "1") (pinfunction "K_1") (pintype "passive"))
      (node (ref "R292") (pin "1") (pinfunction "1_1") (pintype "passive"))
    )
    (net (code "41") (name "Net-(D13-K)") (class "Default")
      (node (ref "D13") (pin "1") (pinfunction "K_1") (pintype "passive"))
      (node (ref "R294") (pin "1") (pinfunction "1_1") (pintype "passive"))
    )
    (net (code "42") (name "Net-(D14-K)") (class "Default")
      (node (ref "D14") (pin "1") (pinfunction "K_1") (pintype "passive"))
      (node (ref "R296") (pin "1") (pinfunction "1_1") (pintype "passive"))
    )
    (net (code "43") (name "Net-(U20A-RSET)") (class "Default")
      (node (ref "R289") (pin "1") (pinfunction "1_1") (pintype "passive"))
      (node (ref "U20") (pin "B14") (pinfunction "RSET_B14") (pintype "input"))
    )
    (net (code "44") (name "Net-(U20A-TRSTn)") (class "Default")
      (node (ref "R288") (pin "1") (pinfunction "1_1") (pintype "passive"))
      (node (ref "U20") (pin "A25") (pinfunction "TRSTn_A25") (pintype "input"))
    )
    (net (code "45") (name "Net-(U20A-TXD0{slash}TD0)") (class "Default")
      (node (ref "R281") (pin "2") (pinfunction "2_2") (pintype "passive"))
      (node (ref "U20") (pin "A6") (pinfunction "TXD0/TD0_A6") (pintype "input"))
      (node (ref "U20") (pin "B6") (pinfunction "TXD1/TD1_B6") (pintype "input"))
      (node (ref "U20") (pin "B7") (pinfunction "TXD2/TD2_B7") (pintype "input"))
      (node (ref "U20") (pin "B8") (pinfunction "TXD3/TD3_B8") (pintype "input"))
    )
    (net (code "46") (name "Net-(U20A-TXD4)") (class "Default")
      (node (ref "R282") (pin "2") (pinfunction "2_2") (pintype "passive"))
      (node (ref "U20") (pin "A10") (pinfunction "TXD6_A10") (pintype "input"))
      (node (ref "U20") (pin "A9") (pinfunction "TXD4_A9") (pintype "input"))
      (node (ref "U20") (pin "B10") (pinfunction "TXD7_B10") (pintype "input"))
      (node (ref "U20") (pin "B9") (pinfunction "TXD5_B9") (pintype "input"))
    )
    (net (code "47") (name "Net-(U20A-XTAL1)") (class "Default")
      (node (ref "U20") (pin "A30") (pinfunction "XTAL1_A30") (pintype "input"))
      (node (ref "U21") (pin "3") (pinfunction "OUTPUT_3") (pintype "passive"))
    )
    (net (code "48") (name "Net-(U21-TRI-STATE)") (class "Default")
      (node (ref "R286") (pin "2") (pinfunction "2_2") (pintype "passive"))
      (node (ref "U21") (pin "1") (pinfunction "TRI-STATE_1") (pintype "passive"))
    )
    (net (code "49") (name "Net-(U22-ADJ)") (class "Default")
      (node (ref "R293") (pin "1") (pinfunction "1_1") (pintype "passive"))
      (node (ref "R295") (pin "2") (pinfunction "2_2") (pintype "passive"))
      (node (ref "U22") (pin "5") (pinfunction "ADJ_5") (pintype "input"))
    )
    (net (code "50") (name "unconnected-(U20A-125CLK-PadB11)") (class "Default")
      (node (ref "U20") (pin "B11") (pinfunction "125CLK_B11") (pintype "output"))
    )
    (net (code "51") (name "unconnected-(U20A-COL{slash}LPBK-PadA45)") (class "Default")
      (node (ref "U20") (pin "A45") (pinfunction "COL/LPBK_A45") (pintype "bidirectional"))
    )
    (net (code "52") (name "unconnected-(U20A-CRS{slash}COMMA-PadB39)") (class "Default")
      (node (ref "U20") (pin "B39") (pinfunction "CRS/COMMA_B39") (pintype "tri_state"))
    )
    (net (code "53") (name "unconnected-(U20A-GTX_CLK{slash}TBI_TXCLK{slash}TXC-PadB4)") (class "Default")
      (node (ref "U20") (pin "B4") (pinfunction "GTX_CLK/TBI_TXCLK/TXC_B4") (pintype "input"))
    )
    (net (code "54") (name "unconnected-(U20A-HSDAC+-PadA20)") (class "Default")
      (node (ref "U20") (pin "A20") (pinfunction "HSDAC+_A20") (pintype "passive"))
    )
    (net (code "55") (name "unconnected-(U20A-HSDAC--PadB18)") (class "Default")
      (node (ref "U20") (pin "B18") (pinfunction "HSDAC-_B18") (pintype "passive"))
    )
    (net (code "56") (name "unconnected-(U20A-LED_DUPLEX-PadB33)") (class "Default")
      (node (ref "U20") (pin "B33") (pinfunction "LED_DUPLEX_B33") (pintype "output"))
    )
    (net (code "57") (name "unconnected-(U20A-NC-PadA7)") (class "Default")
      (node (ref "U20") (pin "A7") (pinfunction "NC_A7") (pintype "passive"))
    )
    (net (code "58") (name "unconnected-(U20A-NC-PadA28)") (class "Default")
      (node (ref "U20") (pin "A28") (pinfunction "NC_A28") (pintype "passive"))
    )
    (net (code "59") (name "unconnected-(U20A-RXD0{slash}RD0-PadA51)") (class "Default")
      (node (ref "U20") (pin "A51") (pinfunction "RXD0/RD0_A51") (pintype "tri_state"))
    )
    (net (code "60") (name "unconnected-(U20A-RXD1{slash}RD1-PadB43)") (class "Default")
      (node (ref "U20") (pin "B43") (pinfunction "RXD1/RD1_B43") (pintype "tri_state"))
    )
    (net (code "61") (name "unconnected-(U20A-RXD2{slash}RD2-PadA50)") (class "Default")
      (node (ref "U20") (pin "A50") (pinfunction "RXD2/RD2_A50") (pintype "tri_state"))
    )
    (net (code "62") (name "unconnected-(U20A-RXD3{slash}RD3-PadA49)") (class "Default")
      (node (ref "U20") (pin "A49") (pinfunction "RXD3/RD3_A49") (pintype "tri_state"))
    )
    (net (code "63") (name "unconnected-(U20A-RXD4-PadB42)") (class "Default")
      (node (ref "U20") (pin "B42") (pinfunction "RXD4_B42") (pintype "tri_state"))
    )
    (net (code "64") (name "unconnected-(U20A-RXD5-PadA48)") (class "Default")
      (node (ref "U20") (pin "A48") (pinfunction "RXD5_A48") (pintype "tri_state"))
    )
    (net (code "65") (name "unconnected-(U20A-RXD6-PadA47)") (class "Default")
      (node (ref "U20") (pin "A47") (pinfunction "RXD6_A47") (pintype "tri_state"))
    )
    (net (code "66") (name "unconnected-(U20A-RXD7-PadB40)") (class "Default")
      (node (ref "U20") (pin "B40") (pinfunction "RXD7_B40") (pintype "tri_state"))
    )
    (net (code "67") (name "unconnected-(U20A-RX_CLK{slash}RCLK0{slash}RXC-PadB1)") (class "Default")
      (node (ref "U20") (pin "B1") (pinfunction "RX_CLK/RCLK0/RXC_B1") (pintype "tri_state"))
    )
    (net (code "68") (name "unconnected-(U20A-RX_DV{slash}RXD8{slash}RX_CTL{slash}RD4_RD9-PadB44)") (class "Default")
      (node (ref "U20") (pin "B44") (pinfunction "RX_DV/RXD8/RX_CTL/RD4_RD9_B44") (pintype "tri_state"))
    )
    (net (code "69") (name "unconnected-(U20A-RX_ER{slash}RXD9-PadA2)") (class "Default")
      (node (ref "U20") (pin "A2") (pinfunction "RX_ER/RXD9_A2") (pintype "tri_state"))
    )
    (net (code "70") (name "unconnected-(U20A-SEL_FREQ-PadB26)") (class "Default")
      (node (ref "U20") (pin "B26") (pinfunction "SEL_FREQ_B26") (pintype "input"))
    )
    (net (code "71") (name "unconnected-(U20A-S_CLK+{slash}SD+-PadA43)") (class "Default")
      (node (ref "U20") (pin "A43") (pinfunction "S_CLK+/SD+_A43") (pintype "bidirectional"))
    )
    (net (code "72") (name "unconnected-(U20A-S_CLK-{slash}SD--PadB37)") (class "Default")
      (node (ref "U20") (pin "B37") (pinfunction "S_CLK-/SD-_B37") (pintype "bidirectional"))
    )
    (net (code "73") (name "unconnected-(U20A-TCK-PadA26)") (class "Default")
      (node (ref "U20") (pin "A26") (pinfunction "TCK_A26") (pintype "input"))
    )
    (net (code "74") (name "unconnected-(U20A-TDI-PadB21)") (class "Default")
      (node (ref "U20") (pin "B21") (pinfunction "TDI_B21") (pintype "input"))
    )
    (net (code "75") (name "unconnected-(U20A-TDO-PadA27)") (class "Default")
      (node (ref "U20") (pin "A27") (pinfunction "TDO_A27") (pintype "output"))
    )
    (net (code "76") (name "unconnected-(U20A-TMS-PadB22)") (class "Default")
      (node (ref "U20") (pin "B22") (pinfunction "TMS_B22") (pintype "input"))
    )
    (net (code "77") (name "unconnected-(U20A-TX_CLK{slash}RCLK1-PadB2)") (class "Default")
      (node (ref "U20") (pin "B2") (pinfunction "TX_CLK/RCLK1_B2") (pintype "tri_state"))
    )
    (net (code "78") (name "unconnected-(U20A-TX_EN{slash}TXD8{slash}TX_CTL{slash}TD4_TD9-PadA5)") (class "Default")
      (node (ref "U20") (pin "A5") (pinfunction "TX_EN/TXD8/TX_CTL/TD4_TD9_A5") (pintype "input"))
    )
    (net (code "79") (name "unconnected-(U20A-TX_ER{slash}TXD9-PadA4)") (class "Default")
      (node (ref "U20") (pin "A4") (pinfunction "TX_ER/TXD9_A4") (pintype "input"))
    )
    (net (code "80") (name "unconnected-(U20A-XTAL2-PadB25)") (class "Default")
      (node (ref "U20") (pin "B25") (pinfunction "XTAL2_B25") (pintype "passive"))
    )
  )
)
